# rel-eeprom-prog.net
KiCad netlist of a schematic drawn in EAGLE
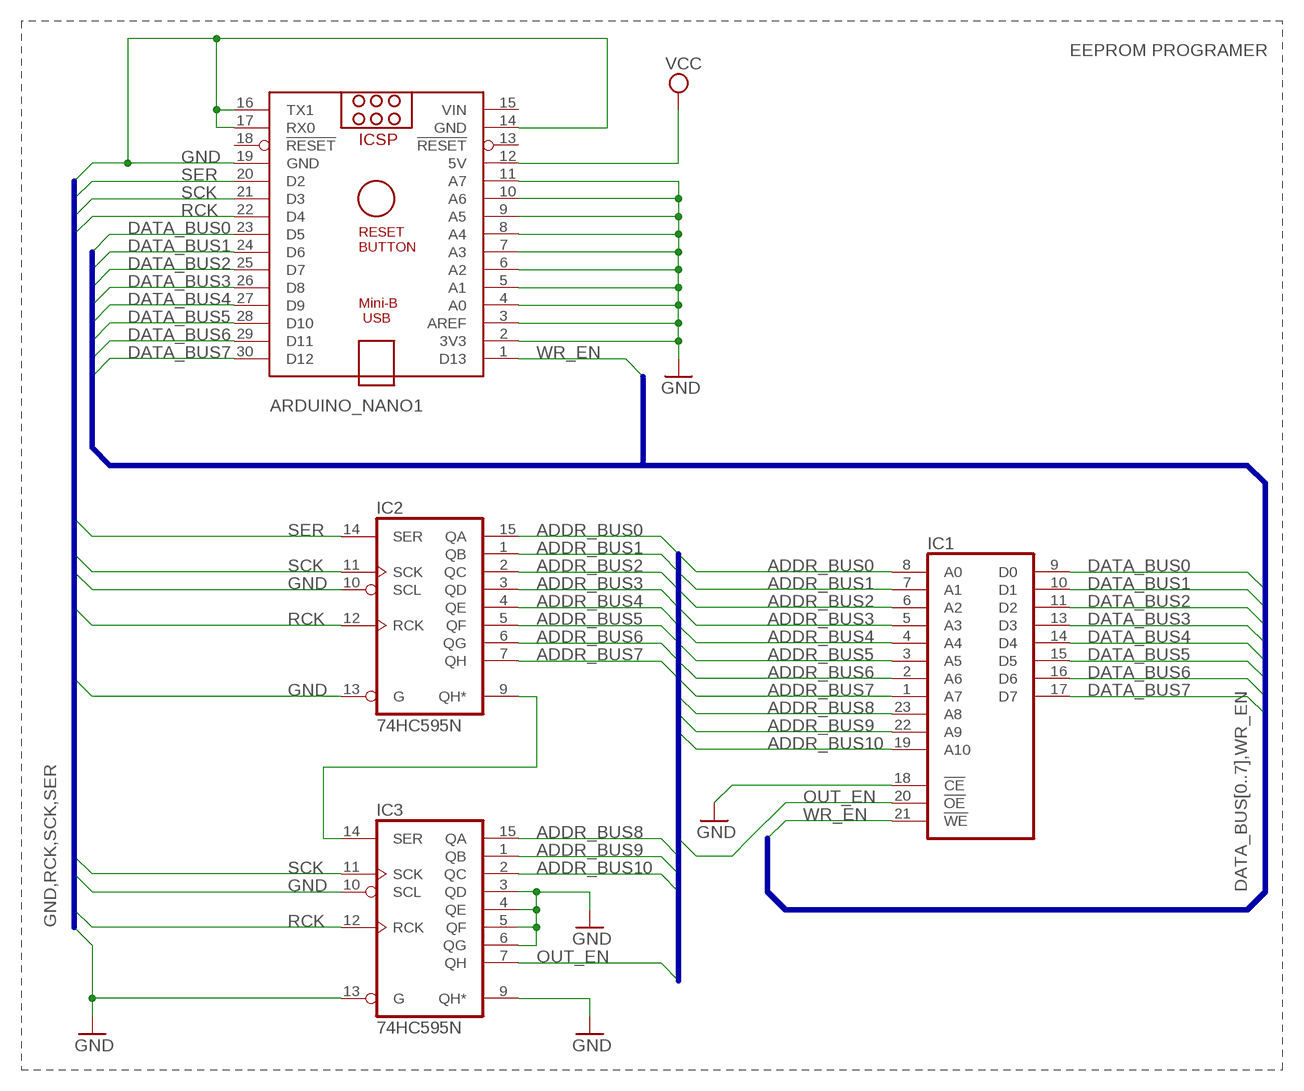
[diagram p0: schematic, sheet 1]

(export (version "E")
  (design (tool "Eeschema 10.0.6"))
  (components
    (comp (ref "ARDUINO_NANO1")
      (value "ARDUINO_NANO")
      (footprint "eagle-import:ARDUINO_NANO")
      (libsource (lib "eagle-import") (part "ARDUINO_NANO"))
    )
    (comp (ref "IC1")
      (value "2816")
      (footprint "eagle-import:DIL24")
      (libsource (lib "eagle-import") (part "2816"))
    )
    (comp (ref "IC2")
      (value "74HC595N")
      (footprint "eagle-import:DIL16")
      (libsource (lib "eagle-import") (part "74595NHC"))
    )
    (comp (ref "IC3")
      (value "74HC595N")
      (footprint "eagle-import:DIL16")
      (libsource (lib "eagle-import") (part "74595NHC"))
    )
  )
  (nets
    (net (code "1") (name "/ADDR_BUS0") (class "Default")
      (node (ref "IC1") (pin "8") (pinfunction "A0_8") (pintype "input"))
      (node (ref "IC2") (pin "15") (pinfunction "QA_15") (pintype "tri_state"))
    )
    (net (code "2") (name "/ADDR_BUS1") (class "Default")
      (node (ref "IC1") (pin "7") (pinfunction "A1_7") (pintype "input"))
      (node (ref "IC2") (pin "1") (pinfunction "QB_1") (pintype "tri_state"))
    )
    (net (code "3") (name "/ADDR_BUS2") (class "Default")
      (node (ref "IC1") (pin "6") (pinfunction "A2_6") (pintype "input"))
      (node (ref "IC2") (pin "2") (pinfunction "QC_2") (pintype "tri_state"))
    )
    (net (code "4") (name "/ADDR_BUS3") (class "Default")
      (node (ref "IC1") (pin "5") (pinfunction "A3_5") (pintype "input"))
      (node (ref "IC2") (pin "3") (pinfunction "QD_3") (pintype "tri_state"))
    )
    (net (code "5") (name "/ADDR_BUS4") (class "Default")
      (node (ref "IC1") (pin "4") (pinfunction "A4_4") (pintype "input"))
      (node (ref "IC2") (pin "4") (pinfunction "QE_4") (pintype "tri_state"))
    )
    (net (code "6") (name "/ADDR_BUS5") (class "Default")
      (node (ref "IC1") (pin "3") (pinfunction "A5_3") (pintype "input"))
      (node (ref "IC2") (pin "5") (pinfunction "QF_5") (pintype "tri_state"))
    )
    (net (code "7") (name "/ADDR_BUS6") (class "Default")
      (node (ref "IC1") (pin "2") (pinfunction "A6_2") (pintype "input"))
      (node (ref "IC2") (pin "6") (pinfunction "QG_6") (pintype "tri_state"))
    )
    (net (code "8") (name "/ADDR_BUS7") (class "Default")
      (node (ref "IC1") (pin "1") (pinfunction "A7_1") (pintype "input"))
      (node (ref "IC2") (pin "7") (pinfunction "QH_7") (pintype "tri_state"))
    )
    (net (code "9") (name "/ADDR_BUS8") (class "Default")
      (node (ref "IC1") (pin "23") (pinfunction "A8_23") (pintype "input"))
      (node (ref "IC3") (pin "15") (pinfunction "QA_15") (pintype "tri_state"))
    )
    (net (code "10") (name "/ADDR_BUS9") (class "Default")
      (node (ref "IC1") (pin "22") (pinfunction "A9_22") (pintype "input"))
      (node (ref "IC3") (pin "1") (pinfunction "QB_1") (pintype "tri_state"))
    )
    (net (code "11") (name "/ADDR_BUS10") (class "Default")
      (node (ref "IC1") (pin "19") (pinfunction "A10_19") (pintype "input"))
      (node (ref "IC3") (pin "2") (pinfunction "QC_2") (pintype "tri_state"))
    )
    (net (code "12") (name "/DATA_BUS0") (class "Default")
      (node (ref "ARDUINO_NANO1") (pin "23") (pinfunction "D5_23") (pintype "bidirectional"))
      (node (ref "IC1") (pin "9") (pinfunction "D0_9") (pintype "bidirectional"))
    )
    (net (code "13") (name "/DATA_BUS1") (class "Default")
      (node (ref "ARDUINO_NANO1") (pin "24") (pinfunction "D6_24") (pintype "bidirectional"))
      (node (ref "IC1") (pin "10") (pinfunction "D1_10") (pintype "bidirectional"))
    )
    (net (code "14") (name "/DATA_BUS2") (class "Default")
      (node (ref "ARDUINO_NANO1") (pin "25") (pinfunction "D7_25") (pintype "bidirectional"))
      (node (ref "IC1") (pin "11") (pinfunction "D2_11") (pintype "bidirectional"))
    )
    (net (code "15") (name "/DATA_BUS3") (class "Default")
      (node (ref "ARDUINO_NANO1") (pin "26") (pinfunction "D8_26") (pintype "bidirectional"))
      (node (ref "IC1") (pin "13") (pinfunction "D3_13") (pintype "bidirectional"))
    )
    (net (code "16") (name "/DATA_BUS4") (class "Default")
      (node (ref "ARDUINO_NANO1") (pin "27") (pinfunction "D9_27") (pintype "bidirectional"))
      (node (ref "IC1") (pin "14") (pinfunction "D4_14") (pintype "bidirectional"))
    )
    (net (code "17") (name "/DATA_BUS5") (class "Default")
      (node (ref "ARDUINO_NANO1") (pin "28") (pinfunction "D10_28") (pintype "bidirectional"))
      (node (ref "IC1") (pin "15") (pinfunction "D5_15") (pintype "bidirectional"))
    )
    (net (code "18") (name "/DATA_BUS6") (class "Default")
      (node (ref "ARDUINO_NANO1") (pin "29") (pinfunction "D11_29") (pintype "bidirectional"))
      (node (ref "IC1") (pin "16") (pinfunction "D6_16") (pintype "bidirectional"))
    )
    (net (code "19") (name "/DATA_BUS7") (class "Default")
      (node (ref "ARDUINO_NANO1") (pin "30") (pinfunction "D12_30") (pintype "bidirectional"))
      (node (ref "IC1") (pin "17") (pinfunction "D7_17") (pintype "bidirectional"))
    )
    (net (code "20") (name "/OUT_EN") (class "Default")
      (node (ref "IC1") (pin "20") (pinfunction "~{OE}_20") (pintype "input"))
      (node (ref "IC3") (pin "7") (pinfunction "QH_7") (pintype "tri_state"))
    )
    (net (code "21") (name "/RCK") (class "Default")
      (node (ref "ARDUINO_NANO1") (pin "22") (pinfunction "D4_22") (pintype "bidirectional"))
      (node (ref "IC2") (pin "12") (pinfunction "RCK_12") (pintype "input"))
      (node (ref "IC3") (pin "12") (pinfunction "RCK_12") (pintype "input"))
    )
    (net (code "22") (name "/SCK") (class "Default")
      (node (ref "ARDUINO_NANO1") (pin "21") (pinfunction "D3_21") (pintype "bidirectional"))
      (node (ref "IC2") (pin "11") (pinfunction "SCK_11") (pintype "input"))
      (node (ref "IC3") (pin "11") (pinfunction "SCK_11") (pintype "input"))
    )
    (net (code "23") (name "/SER") (class "Default")
      (node (ref "ARDUINO_NANO1") (pin "20") (pinfunction "D2_20") (pintype "bidirectional"))
      (node (ref "IC2") (pin "14") (pinfunction "SER_14") (pintype "input"))
    )
    (net (code "24") (name "/VIN") (class "Default")
      (node (ref "ARDUINO_NANO1") (pin "15") (pinfunction "VIN_15") (pintype "power_in"))
    )
    (net (code "25") (name "/WR_EN") (class "Default")
      (node (ref "ARDUINO_NANO1") (pin "1") (pinfunction "D13_1") (pintype "bidirectional"))
      (node (ref "IC1") (pin "21") (pinfunction "~{WE}_21") (pintype "input"))
    )
    (net (code "28") (name "GND") (class "Default")
      (node (ref "ARDUINO_NANO1") (pin "10") (pinfunction "A6_10") (pintype "bidirectional"))
      (node (ref "ARDUINO_NANO1") (pin "11") (pinfunction "A7_11") (pintype "bidirectional"))
      (node (ref "ARDUINO_NANO1") (pin "14") (pinfunction "GND_14") (pintype "power_in"))
      (node (ref "ARDUINO_NANO1") (pin "16") (pinfunction "TX1_16") (pintype "bidirectional"))
      (node (ref "ARDUINO_NANO1") (pin "17") (pinfunction "RX0_17") (pintype "bidirectional"))
      (node (ref "ARDUINO_NANO1") (pin "19") (pinfunction "GND_19") (pintype "power_in"))
      (node (ref "ARDUINO_NANO1") (pin "2") (pinfunction "3V3_2") (pintype "output"))
      (node (ref "ARDUINO_NANO1") (pin "3") (pinfunction "AREF_3") (pintype "input"))
      (node (ref "ARDUINO_NANO1") (pin "4") (pinfunction "A0_4") (pintype "bidirectional"))
      (node (ref "ARDUINO_NANO1") (pin "5") (pinfunction "A1_5") (pintype "bidirectional"))
      (node (ref "ARDUINO_NANO1") (pin "6") (pinfunction "A2_6") (pintype "bidirectional"))
      (node (ref "ARDUINO_NANO1") (pin "7") (pinfunction "A3_7") (pintype "bidirectional"))
      (node (ref "ARDUINO_NANO1") (pin "8") (pinfunction "A4_8") (pintype "bidirectional"))
      (node (ref "ARDUINO_NANO1") (pin "9") (pinfunction "A5_9") (pintype "bidirectional"))
      (node (ref "IC1") (pin "18") (pinfunction "~{CE}_18") (pintype "input"))
      (node (ref "IC2") (pin "10") (pinfunction "SCL_10") (pintype "input"))
      (node (ref "IC2") (pin "13") (pinfunction "G_13") (pintype "input"))
      (node (ref "IC3") (pin "10") (pinfunction "SCL_10") (pintype "input"))
      (node (ref "IC3") (pin "13") (pinfunction "G_13") (pintype "input"))
      (node (ref "IC3") (pin "3") (pinfunction "QD_3") (pintype "tri_state"))
      (node (ref "IC3") (pin "4") (pinfunction "QE_4") (pintype "tri_state"))
      (node (ref "IC3") (pin "5") (pinfunction "QF_5") (pintype "tri_state"))
      (node (ref "IC3") (pin "6") (pinfunction "QG_6") (pintype "tri_state"))
      (node (ref "IC3") (pin "9") (pinfunction "QH*_9") (pintype "tri_state"))
    )
    (net (code "29") (name "Net-(IC2A-QH*)") (class "Default")
      (node (ref "IC2") (pin "9") (pinfunction "QH*_9") (pintype "tri_state"))
      (node (ref "IC3") (pin "14") (pinfunction "SER_14") (pintype "input"))
    )
    (net (code "30") (name "VCC") (class "Default")
      (node (ref "ARDUINO_NANO1") (pin "12") (pinfunction "5V_12") (pintype "power_in"))
    )
    (net (code "31") (name "unconnected-(ARDUINO_NANO1-~{RESET}-Pad13)") (class "Default")
      (node (ref "ARDUINO_NANO1") (pin "13") (pinfunction "~{RESET}_13") (pintype "input"))
    )
    (net (code "32") (name "unconnected-(ARDUINO_NANO1-~{RESET}-Pad18)") (class "Default")
      (node (ref "ARDUINO_NANO1") (pin "18") (pinfunction "~{RESET}_18") (pintype "input"))
    )
  )
)
